# Arduino_V13_5x5.net
KiCad netlist of a schematic drawn in EAGLE
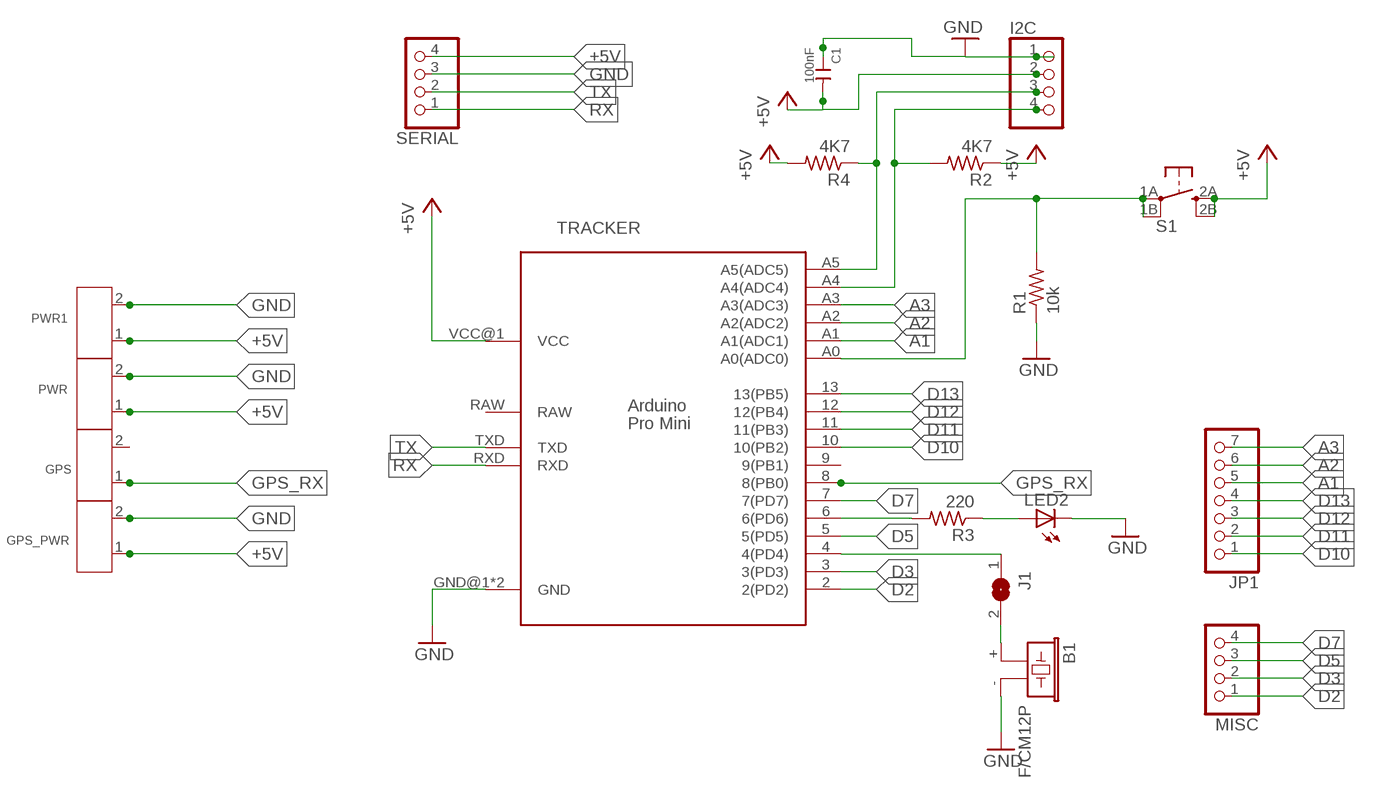
[diagram p0: schematic, sheet 1]

(export (version "E")
  (design (tool "Eeschema 10.0.6"))
  (components
    (comp (ref "B1")
      (value "F/CM12P")
      (footprint "eagle-import:F_CM12P")
      (libsource (lib "eagle-import") (part "F/CM12P"))
    )
    (comp (ref "C1")
      (value "100nF")
      (footprint "eagle-import:C1206")
      (fields (field (name "MPN") "CC1206KKX5R8BB106"))
      (libsource (lib "eagle-import") (part "CERAMIC-10UF-25V-10%-X5R(1206)"))
    )
    (comp (ref "GPS")
      (value "SCREW-TERMINAL-GREEN(2P-3.5)")
      (footprint "eagle-import:H2-3.5-7.0X7.0MM")
      (libsource (lib "eagle-import") (part "SCREW-TERMINAL-GREEN(2P-3.5)"))
    )
    (comp (ref "GPS_PWR")
      (value "SCREW-TERMINAL-GREEN(2P-3.5)")
      (footprint "eagle-import:H2-3.5-7.0X7.0MM")
      (libsource (lib "eagle-import") (part "SCREW-TERMINAL-GREEN(2P-3.5)"))
    )
    (comp (ref "I2C")
      (value "PINHD-1X4")
      (footprint "eagle-import:1X04")
      (libsource (lib "eagle-import") (part "PINHD-1X4"))
    )
    (comp (ref "J1") (value "SJ") (footprint "eagle-import:SJ") (libsource (lib "eagle-import") (part "SJ")))
    (comp (ref "JP1")
      (value "PINHD-1X7")
      (footprint "eagle-import:1X07")
      (libsource (lib "eagle-import") (part "PINHD-1X7"))
    )
    (comp (ref "LED2")
      (value "LED5MM")
      (footprint "eagle-import:LED5MM")
      (libsource (lib "eagle-import") (part "LED5MM"))
    )
    (comp (ref "MISC")
      (value "PINHD-1X4")
      (footprint "eagle-import:1X04")
      (libsource (lib "eagle-import") (part "PINHD-1X4"))
    )
    (comp (ref "PWR")
      (value "SCREW-TERMINAL-GREEN(2P-3.5)")
      (footprint "eagle-import:H2-3.5-7.0X7.0MM")
      (libsource (lib "eagle-import") (part "SCREW-TERMINAL-GREEN(2P-3.5)"))
    )
    (comp (ref "PWR1")
      (value "SCREW-TERMINAL-GREEN(2P-3.5)")
      (footprint "eagle-import:H2-3.5-7.0X7.0MM")
      (libsource (lib "eagle-import") (part "SCREW-TERMINAL-GREEN(2P-3.5)"))
    )
    (comp (ref "R1")
      (value "10k")
      (footprint "eagle-import:M1206")
      (libsource (lib "eagle-import") (part "R-US_M1206"))
    )
    (comp (ref "R2")
      (value "4K7")
      (footprint "eagle-import:M1206")
      (libsource (lib "eagle-import") (part "R-US_M1206"))
    )
    (comp (ref "R3")
      (value "220")
      (footprint "eagle-import:M1206")
      (libsource (lib "eagle-import") (part "R-US_M1206"))
    )
    (comp (ref "R4")
      (value "4K7")
      (footprint "eagle-import:M1206")
      (libsource (lib "eagle-import") (part "R-US_M1206"))
    )
    (comp (ref "S1")
      (value "TACTILETACT-6X6-PTH")
      (footprint "eagle-import:TACTILE-PTH")
      (libsource (lib "eagle-import") (part "TACTILETACT-6X6-PTH"))
    )
    (comp (ref "SERIAL")
      (value "PINHD-1X4")
      (footprint "eagle-import:1X04")
      (libsource (lib "eagle-import") (part "PINHD-1X4"))
    )
    (comp (ref "TRACKER")
      (value "PRO-MINI")
      (footprint "eagle-import:PRO-MINI")
      (libsource (lib "eagle-import") (part "PRO-MINI"))
    )
  )
  (nets
    (net (code "1") (name "+5V") (class "Default")
      (node (ref "C1") (pin "2") (pinfunction "2_2") (pintype "passive"))
      (node (ref "GPS_PWR") (pin "1") (pinfunction "1_1") (pintype "bidirectional"))
      (node (ref "I2C") (pin "2") (pinfunction "2_2") (pintype "passive"))
      (node (ref "PWR") (pin "1") (pinfunction "1_1") (pintype "bidirectional"))
      (node (ref "PWR1") (pin "1") (pinfunction "1_1") (pintype "bidirectional"))
      (node (ref "R2") (pin "1") (pinfunction "1_1") (pintype "passive"))
      (node (ref "R4") (pin "2") (pinfunction "2_2") (pintype "passive"))
      (node (ref "S1") (pin "2A") (pinfunction "2A_2A") (pintype "passive"))
      (node (ref "S1") (pin "2B") (pinfunction "2B_2B") (pintype "passive"))
      (node (ref "SERIAL") (pin "4") (pinfunction "4_4") (pintype "passive"))
      (node (ref "TRACKER") (pin "VCC@1") (pinfunction "VCC_VCC@1") (pintype "bidirectional"))
    )
    (net (code "2") (name "A1") (class "Default")
      (node (ref "JP1") (pin "5") (pinfunction "5_5") (pintype "passive"))
      (node (ref "TRACKER") (pin "A1") (pinfunction "A1(ADC1)_A1") (pintype "bidirectional"))
    )
    (net (code "3") (name "A2") (class "Default")
      (node (ref "JP1") (pin "6") (pinfunction "6_6") (pintype "passive"))
      (node (ref "TRACKER") (pin "A2") (pinfunction "A2(ADC2)_A2") (pintype "bidirectional"))
    )
    (net (code "4") (name "A3") (class "Default")
      (node (ref "JP1") (pin "7") (pinfunction "7_7") (pintype "passive"))
      (node (ref "TRACKER") (pin "A3") (pinfunction "A3(ADC3)_A3") (pintype "bidirectional"))
    )
    (net (code "5") (name "D2") (class "Default")
      (node (ref "MISC") (pin "1") (pinfunction "1_1") (pintype "passive"))
      (node (ref "TRACKER") (pin "2") (pinfunction "2(PD2)_2") (pintype "bidirectional"))
    )
    (net (code "6") (name "D3") (class "Default")
      (node (ref "MISC") (pin "2") (pinfunction "2_2") (pintype "passive"))
      (node (ref "TRACKER") (pin "3") (pinfunction "3(PD3)_3") (pintype "bidirectional"))
    )
    (net (code "7") (name "D5") (class "Default")
      (node (ref "MISC") (pin "3") (pinfunction "3_3") (pintype "passive"))
      (node (ref "TRACKER") (pin "5") (pinfunction "5(PD5)_5") (pintype "bidirectional"))
    )
    (net (code "8") (name "D7") (class "Default")
      (node (ref "MISC") (pin "4") (pinfunction "4_4") (pintype "passive"))
      (node (ref "TRACKER") (pin "7") (pinfunction "7(PD7)_7") (pintype "bidirectional"))
    )
    (net (code "9") (name "D10") (class "Default")
      (node (ref "JP1") (pin "1") (pinfunction "1_1") (pintype "passive"))
      (node (ref "TRACKER") (pin "10") (pinfunction "10(PB2)_10") (pintype "bidirectional"))
    )
    (net (code "10") (name "D11") (class "Default")
      (node (ref "JP1") (pin "2") (pinfunction "2_2") (pintype "passive"))
      (node (ref "TRACKER") (pin "11") (pinfunction "11(PB3)_11") (pintype "bidirectional"))
    )
    (net (code "11") (name "D12") (class "Default")
      (node (ref "JP1") (pin "3") (pinfunction "3_3") (pintype "passive"))
      (node (ref "TRACKER") (pin "12") (pinfunction "12(PB4)_12") (pintype "bidirectional"))
    )
    (net (code "12") (name "D13") (class "Default")
      (node (ref "JP1") (pin "4") (pinfunction "4_4") (pintype "passive"))
      (node (ref "TRACKER") (pin "13") (pinfunction "13(PB5)_13") (pintype "bidirectional"))
    )
    (net (code "13") (name "GND") (class "Default")
      (node (ref "B1") (pin "-") (pinfunction "2_-") (pintype "passive"))
      (node (ref "C1") (pin "1") (pinfunction "1_1") (pintype "passive"))
      (node (ref "GPS_PWR") (pin "2") (pinfunction "2_2") (pintype "bidirectional"))
      (node (ref "I2C") (pin "1") (pinfunction "1_1") (pintype "passive"))
      (node (ref "LED2") (pin "K") (pinfunction "C_K") (pintype "passive"))
      (node (ref "PWR") (pin "2") (pinfunction "2_2") (pintype "bidirectional"))
      (node (ref "PWR1") (pin "2") (pinfunction "2_2") (pintype "bidirectional"))
      (node (ref "R1") (pin "1") (pinfunction "1_1") (pintype "passive"))
      (node (ref "SERIAL") (pin "3") (pinfunction "3_3") (pintype "passive"))
      (node (ref "TRACKER") (pin "GND@1") (pinfunction "GND_GND@1") (pintype "bidirectional"))
      (node (ref "TRACKER") (pin "GND@2") (pinfunction "GND_GND@2") (pintype "bidirectional"))
    )
    (net (code "14") (name "GPS_RX") (class "Default")
      (node (ref "GPS") (pin "1") (pinfunction "1_1") (pintype "bidirectional"))
      (node (ref "TRACKER") (pin "8") (pinfunction "8(PB0)_8") (pintype "bidirectional"))
    )
    (net (code "15") (name "Net-(B1-1)") (class "Default")
      (node (ref "B1") (pin "+") (pinfunction "1_+") (pintype "passive"))
      (node (ref "J1") (pin "2") (pinfunction "2_2") (pintype "passive"))
    )
    (net (code "16") (name "Net-(LED2-PadA)") (class "Default")
      (node (ref "LED2") (pin "A") (pinfunction "A_A") (pintype "passive"))
      (node (ref "R3") (pin "1") (pinfunction "1_1") (pintype "passive"))
    )
    (net (code "17") (name "Net-(TRACKER-4(PD4))") (class "Default")
      (node (ref "J1") (pin "1") (pinfunction "1_1") (pintype "passive"))
      (node (ref "TRACKER") (pin "4") (pinfunction "4(PD4)_4") (pintype "bidirectional"))
    )
    (net (code "18") (name "Net-(TRACKER-6(PD6))") (class "Default")
      (node (ref "R3") (pin "2") (pinfunction "2_2") (pintype "passive"))
      (node (ref "TRACKER") (pin "6") (pinfunction "6(PD6)_6") (pintype "bidirectional"))
    )
    (net (code "19") (name "Net-(TRACKER-A0(ADC0))") (class "Default")
      (node (ref "R1") (pin "2") (pinfunction "2_2") (pintype "passive"))
      (node (ref "S1") (pin "1A") (pinfunction "1A_1A") (pintype "passive"))
      (node (ref "S1") (pin "1B") (pinfunction "1B_1B") (pintype "passive"))
      (node (ref "TRACKER") (pin "A0") (pinfunction "A0(ADC0)_A0") (pintype "bidirectional"))
    )
    (net (code "20") (name "Net-(TRACKER-A4(ADC4))") (class "Default")
      (node (ref "I2C") (pin "4") (pinfunction "4_4") (pintype "passive"))
      (node (ref "R2") (pin "2") (pinfunction "2_2") (pintype "passive"))
      (node (ref "TRACKER") (pin "A4") (pinfunction "A4(ADC4)_A4") (pintype "bidirectional"))
    )
    (net (code "21") (name "Net-(TRACKER-A5(ADC5))") (class "Default")
      (node (ref "I2C") (pin "3") (pinfunction "3_3") (pintype "passive"))
      (node (ref "R4") (pin "1") (pinfunction "1_1") (pintype "passive"))
      (node (ref "TRACKER") (pin "A5") (pinfunction "A5(ADC5)_A5") (pintype "bidirectional"))
    )
    (net (code "22") (name "RX") (class "Default")
      (node (ref "SERIAL") (pin "1") (pinfunction "1_1") (pintype "passive"))
      (node (ref "TRACKER") (pin "RXD") (pinfunction "RXD_RXD") (pintype "bidirectional"))
    )
    (net (code "23") (name "TX") (class "Default")
      (node (ref "SERIAL") (pin "2") (pinfunction "2_2") (pintype "passive"))
      (node (ref "TRACKER") (pin "TXD") (pinfunction "TXD_TXD") (pintype "bidirectional"))
    )
    (net (code "24") (name "unconnected-(GPS-Pad2)") (class "Default")
      (node (ref "GPS") (pin "2") (pinfunction "2_2") (pintype "bidirectional"))
    )
    (net (code "25") (name "unconnected-(TRACKER-9(PB1)-Pad9)") (class "Default")
      (node (ref "TRACKER") (pin "9") (pinfunction "9(PB1)_9") (pintype "bidirectional"))
    )
    (net (code "26") (name "unconnected-(TRACKER-PadRAW)") (class "Default")
      (node (ref "TRACKER") (pin "RAW") (pinfunction "RAW_RAW") (pintype "bidirectional"))
    )
  )
)
